# 1.net
KiCad netlist of a schematic drawn in Altium Designer
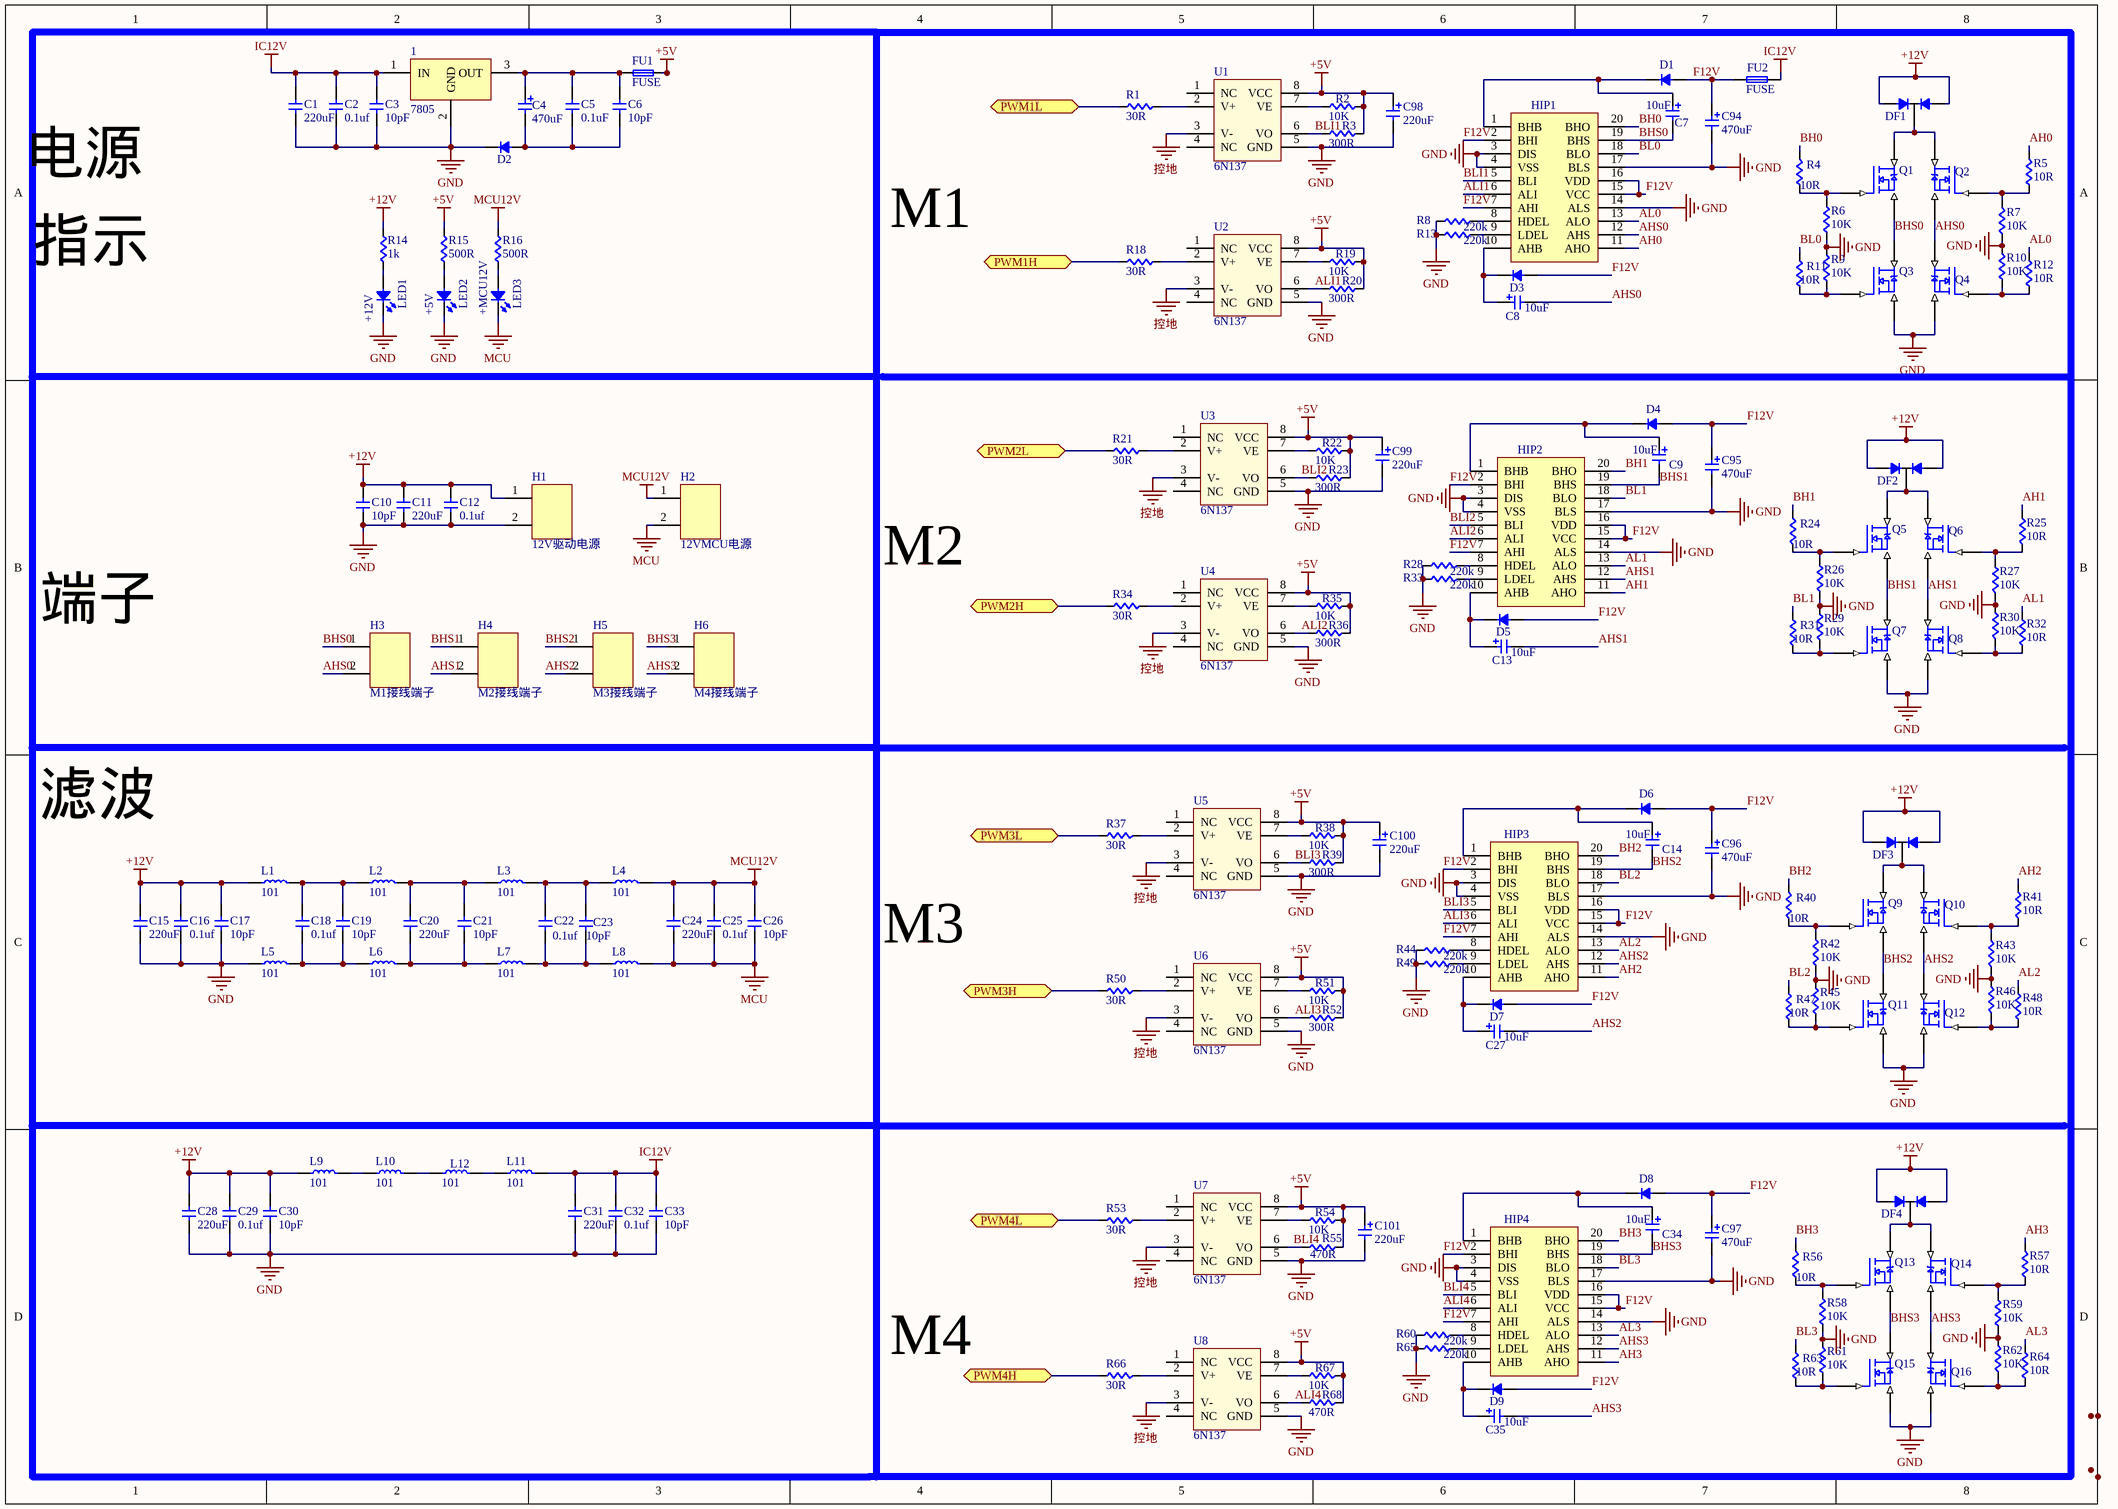
[diagram p0: 小车主板原理图1.SchDoc]

(export (version "E")
  (design (tool "Eeschema 10.0.6"))
  (components
    (comp (ref "1") (value "7805") (footprint "TO-252-2") (libsource (lib "史福祥库") (part "78XX")))
    (comp (ref "C1") (value "220uF") (footprint "CD-8*8-无极性") (libsource (lib "史福祥库") (part "C")))
    (comp (ref "C2") (value "0.1uf") (footprint "0805C") (libsource (lib "史福祥库") (part "C")))
    (comp (ref "C3") (value "10pF") (footprint "0805C") (libsource (lib "史福祥库") (part "C")))
    (comp (ref "C4")
      (value "470uF")
      (footprint "CD-8*8-2")
      (fields (field (name "PUBLISHER") "Altium Limited"))
      (libsource (lib "史福祥库") (part "C+"))
    )
    (comp (ref "C5") (value "0.1uF") (footprint "0805C") (libsource (lib "史福祥库") (part "C")))
    (comp (ref "C6") (value "10pF") (footprint "0805C") (libsource (lib "史福祥库") (part "C")))
    (comp (ref "C7")
      (value "10uF")
      (footprint "CD-8*8-2")
      (fields (field (name "PUBLISHER") "Altium Limited"))
      (libsource (lib "史福祥库") (part "C+"))
    )
    (comp (ref "C8")
      (value "10uF")
      (footprint "CD-8*8-2")
      (fields (field (name "PUBLISHER") "Altium Limited"))
      (libsource (lib "史福祥库") (part "C+"))
    )
    (comp (ref "C9")
      (value "10uF")
      (footprint "CD-8*8-2")
      (fields (field (name "PUBLISHER") "Altium Limited"))
      (libsource (lib "史福祥库") (part "C+"))
    )
    (comp (ref "C10") (value "10pF") (footprint "0805C") (libsource (lib "史福祥库") (part "C")))
    (comp (ref "C11") (value "220uF") (footprint "CD-8*8-无极性") (libsource (lib "史福祥库") (part "C")))
    (comp (ref "C12") (value "0.1uf") (footprint "0805C") (libsource (lib "史福祥库") (part "C")))
    (comp (ref "C13")
      (value "10uF")
      (footprint "CD-8*8-2")
      (fields (field (name "PUBLISHER") "Altium Limited"))
      (libsource (lib "史福祥库") (part "C+"))
    )
    (comp (ref "C14")
      (value "10uF")
      (footprint "CD-8*8-2")
      (fields (field (name "PUBLISHER") "Altium Limited"))
      (libsource (lib "史福祥库") (part "C+"))
    )
    (comp (ref "C15") (value "220uF") (footprint "CD-8*8-无极性") (libsource (lib "史福祥库") (part "C")))
    (comp (ref "C16") (value "0.1uf") (footprint "0805C") (libsource (lib "史福祥库") (part "C")))
    (comp (ref "C17") (value "10pF") (footprint "0805C") (libsource (lib "史福祥库") (part "C")))
    (comp (ref "C18") (value "0.1uf") (footprint "0805C") (libsource (lib "史福祥库") (part "C")))
    (comp (ref "C19") (value "10pF") (footprint "0805C") (libsource (lib "史福祥库") (part "C")))
    (comp (ref "C20") (value "220uF") (footprint "CD-8*8-无极性") (libsource (lib "史福祥库") (part "C")))
    (comp (ref "C21") (value "10pF") (footprint "0805C") (libsource (lib "史福祥库") (part "C")))
    (comp (ref "C22") (value "0.1uf") (footprint "0805C") (libsource (lib "史福祥库") (part "C")))
    (comp (ref "C23") (value "10pF") (footprint "0805C") (libsource (lib "史福祥库") (part "C")))
    (comp (ref "C24") (value "220uF") (footprint "CD-8*8-无极性") (libsource (lib "史福祥库") (part "C")))
    (comp (ref "C25") (value "0.1uf") (footprint "0805C") (libsource (lib "史福祥库") (part "C")))
    (comp (ref "C26") (value "10pF") (footprint "0805C") (libsource (lib "史福祥库") (part "C")))
    (comp (ref "C27")
      (value "10uF")
      (footprint "CD-8*8-2")
      (fields (field (name "PUBLISHER") "Altium Limited"))
      (libsource (lib "史福祥库") (part "C+"))
    )
    (comp (ref "C28") (value "220uF") (footprint "CD-8*8-无极性") (libsource (lib "史福祥库") (part "C")))
    (comp (ref "C29") (value "0.1uf") (footprint "0805C") (libsource (lib "史福祥库") (part "C")))
    (comp (ref "C30") (value "10pF") (footprint "0805C") (libsource (lib "史福祥库") (part "C")))
    (comp (ref "C31") (value "220uF") (footprint "CD-8*8-无极性") (libsource (lib "史福祥库") (part "C")))
    (comp (ref "C32") (value "0.1uf") (footprint "0805C") (libsource (lib "史福祥库") (part "C")))
    (comp (ref "C33") (value "10pF") (footprint "0805C") (libsource (lib "史福祥库") (part "C")))
    (comp (ref "C34")
      (value "10uF")
      (footprint "CD-8*8-2")
      (fields (field (name "PUBLISHER") "Altium Limited"))
      (libsource (lib "史福祥库") (part "C+"))
    )
    (comp (ref "C35")
      (value "10uF")
      (footprint "CD-8*8-2")
      (fields (field (name "PUBLISHER") "Altium Limited"))
      (libsource (lib "史福祥库") (part "C+"))
    )
    (comp (ref "C94")
      (value "470uF")
      (footprint "CD-8*8-2")
      (fields (field (name "PUBLISHER") "Altium Limited"))
      (libsource (lib "史福祥库") (part "C+"))
    )
    (comp (ref "C95")
      (value "470uF")
      (footprint "CD-8*8-2")
      (fields (field (name "PUBLISHER") "Altium Limited"))
      (libsource (lib "史福祥库") (part "C+"))
    )
    (comp (ref "C96")
      (value "470uF")
      (footprint "CD-8*8-2")
      (fields (field (name "PUBLISHER") "Altium Limited"))
      (libsource (lib "史福祥库") (part "C+"))
    )
    (comp (ref "C97")
      (value "470uF")
      (footprint "CD-8*8-2")
      (fields (field (name "PUBLISHER") "Altium Limited"))
      (libsource (lib "史福祥库") (part "C+"))
    )
    (comp (ref "C98")
      (value "220uF")
      (footprint "CD-8*8-2")
      (fields (field (name "PUBLISHER") "Altium Limited"))
      (libsource (lib "史福祥库") (part "C+"))
    )
    (comp (ref "C99")
      (value "220uF")
      (footprint "CD-8*8-2")
      (fields (field (name "PUBLISHER") "Altium Limited"))
      (libsource (lib "史福祥库") (part "C+"))
    )
    (comp (ref "C100")
      (value "220uF")
      (footprint "CD-8*8-2")
      (fields (field (name "PUBLISHER") "Altium Limited"))
      (libsource (lib "史福祥库") (part "C+"))
    )
    (comp (ref "C101")
      (value "220uF")
      (footprint "CD-8*8-2")
      (fields (field (name "PUBLISHER") "Altium Limited"))
      (libsource (lib "史福祥库") (part "C+"))
    )
    (comp (ref "D1")
      (value "D")
      (footprint "DO-214-M7-  4007贴片")
      (fields (field (name "PUBLISHER") "Altium Limited"))
      (libsource (lib "史福祥库") (part "D"))
    )
    (comp (ref "D2")
      (value "D")
      (footprint "DO-214-M7-  4007贴片")
      (fields (field (name "PUBLISHER") "Altium Limited"))
      (libsource (lib "史福祥库") (part "D"))
    )
    (comp (ref "D3")
      (value "D")
      (footprint "DO-214-M7-  4007贴片")
      (fields (field (name "PUBLISHER") "Altium Limited"))
      (libsource (lib "史福祥库") (part "D"))
    )
    (comp (ref "D4")
      (value "D")
      (footprint "DO-214-M7-  4007贴片")
      (fields (field (name "PUBLISHER") "Altium Limited"))
      (libsource (lib "史福祥库") (part "D"))
    )
    (comp (ref "D5")
      (value "D")
      (footprint "DO-214-M7-  4007贴片")
      (fields (field (name "PUBLISHER") "Altium Limited"))
      (libsource (lib "史福祥库") (part "D"))
    )
    (comp (ref "D6")
      (value "D")
      (footprint "DO-214-M7-  4007贴片")
      (fields (field (name "PUBLISHER") "Altium Limited"))
      (libsource (lib "史福祥库") (part "D"))
    )
    (comp (ref "D7")
      (value "D")
      (footprint "DO-214-M7-  4007贴片")
      (fields (field (name "PUBLISHER") "Altium Limited"))
      (libsource (lib "史福祥库") (part "D"))
    )
    (comp (ref "D8")
      (value "D")
      (footprint "DO-214-M7-  4007贴片")
      (fields (field (name "PUBLISHER") "Altium Limited"))
      (libsource (lib "史福祥库") (part "D"))
    )
    (comp (ref "D9")
      (value "D")
      (footprint "DO-214-M7-  4007贴片")
      (fields (field (name "PUBLISHER") "Altium Limited"))
      (libsource (lib "史福祥库") (part "D"))
    )
    (comp (ref "DF1") (value "DF?") (footprint "TO263") (libsource (lib "史福祥库") (part "D复合二极管")))
    (comp (ref "DF2") (value "DF?") (footprint "TO263") (libsource (lib "史福祥库") (part "D复合二极管")))
    (comp (ref "DF3") (value "DF?") (footprint "TO263") (libsource (lib "史福祥库") (part "D复合二极管")))
    (comp (ref "DF4") (value "DF?") (footprint "TO263") (libsource (lib "史福祥库") (part "D复合二极管")))
    (comp (ref "FU1") (value "FUSE") (footprint "1206") (libsource (lib "史福祥库") (part "FUSE")))
    (comp (ref "FU2") (value "FUSE") (footprint "1206") (libsource (lib "史福祥库") (part "FUSE")))
    (comp (ref "H1") (value "12V驱动电源") (footprint "KF301接线端子") (libsource (lib "史福祥库") (part "KF301 接线端子")))
    (comp (ref "H2") (value "12VMCU电源") (footprint "KF301接线端子") (libsource (lib "史福祥库") (part "KF301 接线端子")))
    (comp (ref "H3") (value "M1接线端子") (footprint "KF301接线端子") (libsource (lib "史福祥库") (part "KF301 接线端子")))
    (comp (ref "H4") (value "M2接线端子") (footprint "KF301接线端子") (libsource (lib "史福祥库") (part "KF301 接线端子")))
    (comp (ref "H5") (value "M3接线端子") (footprint "KF301接线端子") (libsource (lib "史福祥库") (part "KF301 接线端子")))
    (comp (ref "H6") (value "M4接线端子") (footprint "KF301接线端子") (libsource (lib "史福祥库") (part "KF301 接线端子")))
    (comp (ref "HIP1") (value "HIP4081") (footprint "SOP-20..") (libsource (lib "史福祥库") (part "HIP4081")))
    (comp (ref "HIP2") (value "HIP4081") (footprint "SOP-20..") (libsource (lib "史福祥库") (part "HIP4081")))
    (comp (ref "HIP3") (value "HIP4081") (footprint "SOP-20..") (libsource (lib "史福祥库") (part "HIP4081")))
    (comp (ref "HIP4") (value "HIP4081") (footprint "SOP-20..") (libsource (lib "史福祥库") (part "HIP4081")))
    (comp (ref "L1")
      (value "101")
      (footprint "12*12电感")
      (fields (field (name "Comment") "L") (field (name "PUBLISHER") "Altium Limited"))
      (libsource (lib "史福祥库") (part "L"))
    )
    (comp (ref "L2")
      (value "101")
      (footprint "12*12电感")
      (fields (field (name "Comment") "L") (field (name "PUBLISHER") "Altium Limited"))
      (libsource (lib "史福祥库") (part "L"))
    )
    (comp (ref "L3")
      (value "101")
      (footprint "12*12电感")
      (fields (field (name "Comment") "L") (field (name "PUBLISHER") "Altium Limited"))
      (libsource (lib "史福祥库") (part "L"))
    )
    (comp (ref "L4")
      (value "101")
      (footprint "12*12电感")
      (fields (field (name "Comment") "L") (field (name "PUBLISHER") "Altium Limited"))
      (libsource (lib "史福祥库") (part "L"))
    )
    (comp (ref "L5")
      (value "101")
      (footprint "12*12电感")
      (fields (field (name "Comment") "L") (field (name "PUBLISHER") "Altium Limited"))
      (libsource (lib "史福祥库") (part "L"))
    )
    (comp (ref "L6")
      (value "101")
      (footprint "12*12电感")
      (fields (field (name "Comment") "L") (field (name "PUBLISHER") "Altium Limited"))
      (libsource (lib "史福祥库") (part "L"))
    )
    (comp (ref "L7")
      (value "101")
      (footprint "12*12电感")
      (fields (field (name "Comment") "L") (field (name "PUBLISHER") "Altium Limited"))
      (libsource (lib "史福祥库") (part "L"))
    )
    (comp (ref "L8")
      (value "101")
      (footprint "12*12电感")
      (fields (field (name "Comment") "L") (field (name "PUBLISHER") "Altium Limited"))
      (libsource (lib "史福祥库") (part "L"))
    )
    (comp (ref "L9")
      (value "101")
      (footprint "12*12电感")
      (fields (field (name "Comment") "L") (field (name "PUBLISHER") "Altium Limited"))
      (libsource (lib "史福祥库") (part "L"))
    )
    (comp (ref "L10")
      (value "101")
      (footprint "12*12电感")
      (fields (field (name "Comment") "L") (field (name "PUBLISHER") "Altium Limited"))
      (libsource (lib "史福祥库") (part "L"))
    )
    (comp (ref "L11")
      (value "101")
      (footprint "12*12电感")
      (fields (field (name "Comment") "L") (field (name "PUBLISHER") "Altium Limited"))
      (libsource (lib "史福祥库") (part "L"))
    )
    (comp (ref "L12")
      (value "101")
      (footprint "12*12电感")
      (fields (field (name "Comment") "L") (field (name "PUBLISHER") "Altium Limited"))
      (libsource (lib "史福祥库") (part "L"))
    )
    (comp (ref "LED1")
      (value "+12V")
      (footprint "0805D")
      (fields (field (name "PUBLISHER") "Altium Limited"))
      (libsource (lib "史福祥库") (part "LED"))
    )
    (comp (ref "LED2")
      (value "+5V")
      (footprint "0805D")
      (fields (field (name "PUBLISHER") "Altium Limited"))
      (libsource (lib "史福祥库") (part "LED"))
    )
    (comp (ref "LED3")
      (value "+MCU12V")
      (footprint "0805D")
      (fields (field (name "PUBLISHER") "Altium Limited"))
      (libsource (lib "史福祥库") (part "LED"))
    )
    (comp (ref "Q1") (value "IRFP260N") (footprint "TO-247 - 贴") (libsource (lib "史福祥库") (part "IRFP260N")))
    (comp (ref "Q2") (value "IRFP260N") (footprint "TO-247 - 贴") (libsource (lib "史福祥库") (part "IRFP260N")))
    (comp (ref "Q3") (value "IRFP260N") (footprint "TO-247 - 贴") (libsource (lib "史福祥库") (part "IRFP260N")))
    (comp (ref "Q4") (value "IRFP260N") (footprint "TO-247 - 贴") (libsource (lib "史福祥库") (part "IRFP260N")))
    (comp (ref "Q5") (value "IRFP260N") (footprint "TO-247 - 贴") (libsource (lib "史福祥库") (part "IRFP260N")))
    (comp (ref "Q6") (value "IRFP260N") (footprint "TO-247 - 贴") (libsource (lib "史福祥库") (part "IRFP260N")))
    (comp (ref "Q7") (value "IRFP260N") (footprint "TO-247 - 贴") (libsource (lib "史福祥库") (part "IRFP260N")))
    (comp (ref "Q8") (value "IRFP260N") (footprint "TO-247 - 贴") (libsource (lib "史福祥库") (part "IRFP260N")))
    (comp (ref "Q9") (value "IRFP260N") (footprint "TO-247 - 贴") (libsource (lib "史福祥库") (part "IRFP260N")))
    (comp (ref "Q10") (value "IRFP260N") (footprint "TO-247 - 贴") (libsource (lib "史福祥库") (part "IRFP260N")))
    (comp (ref "Q11") (value "IRFP260N") (footprint "TO-247 - 贴") (libsource (lib "史福祥库") (part "IRFP260N")))
    (comp (ref "Q12") (value "IRFP260N") (footprint "TO-247 - 贴") (libsource (lib "史福祥库") (part "IRFP260N")))
    (comp (ref "Q13") (value "IRFP260N") (footprint "TO-247 - 贴") (libsource (lib "史福祥库") (part "IRFP260N")))
    (comp (ref "Q14") (value "IRFP260N") (footprint "TO-247 - 贴") (libsource (lib "史福祥库") (part "IRFP260N")))
    (comp (ref "Q15") (value "IRFP260N") (footprint "TO-247 - 贴") (libsource (lib "史福祥库") (part "IRFP260N")))
    (comp (ref "Q16") (value "IRFP260N") (footprint "TO-247 - 贴") (libsource (lib "史福祥库") (part "IRFP260N")))
    (comp (ref "R1") (value "30R") (footprint "0805") (libsource (lib "史福祥库") (part "Res")))
    (comp (ref "R2") (value "10K") (footprint "0805") (libsource (lib "史福祥库") (part "Res")))
    (comp (ref "R3") (value "300R") (footprint "0805") (libsource (lib "史福祥库") (part "Res")))
    (comp (ref "R4") (value "10R") (footprint "0805") (libsource (lib "史福祥库") (part "Res")))
    (comp (ref "R5") (value "10R") (footprint "0805") (libsource (lib "史福祥库") (part "Res")))
    (comp (ref "R6") (value "10K") (footprint "0805") (libsource (lib "史福祥库") (part "Res")))
    (comp (ref "R7") (value "10K") (footprint "0805") (libsource (lib "史福祥库") (part "Res")))
    (comp (ref "R8") (value "220k") (footprint "0805") (libsource (lib "史福祥库") (part "Res")))
    (comp (ref "R9") (value "10K") (footprint "0805") (libsource (lib "史福祥库") (part "Res")))
    (comp (ref "R10") (value "10K") (footprint "0805") (libsource (lib "史福祥库") (part "Res")))
    (comp (ref "R11") (value "10R") (footprint "0805") (libsource (lib "史福祥库") (part "Res")))
    (comp (ref "R12") (value "10R") (footprint "0805") (libsource (lib "史福祥库") (part "Res")))
    (comp (ref "R13") (value "220k") (footprint "0805") (libsource (lib "史福祥库") (part "Res")))
    (comp (ref "R14") (value "1k") (footprint "0805") (libsource (lib "史福祥库") (part "Res")))
    (comp (ref "R15") (value "500R") (footprint "0805") (libsource (lib "史福祥库") (part "Res")))
    (comp (ref "R16") (value "500R") (footprint "0805") (libsource (lib "史福祥库") (part "Res")))
    (comp (ref "R18") (value "30R") (footprint "0805") (libsource (lib "史福祥库") (part "Res")))
    (comp (ref "R19") (value "10K") (footprint "0805") (libsource (lib "史福祥库") (part "Res")))
    (comp (ref "R20") (value "300R") (footprint "0805") (libsource (lib "史福祥库") (part "Res")))
    (comp (ref "R21") (value "30R") (footprint "0805") (libsource (lib "史福祥库") (part "Res")))
    (comp (ref "R22") (value "10K") (footprint "0805") (libsource (lib "史福祥库") (part "Res")))
    (comp (ref "R23") (value "300R") (footprint "0805") (libsource (lib "史福祥库") (part "Res")))
    (comp (ref "R24") (value "10R") (footprint "0805") (libsource (lib "史福祥库") (part "Res")))
    (comp (ref "R25") (value "10R") (footprint "0805") (libsource (lib "史福祥库") (part "Res")))
    (comp (ref "R26") (value "10K") (footprint "0805") (libsource (lib "史福祥库") (part "Res")))
    (comp (ref "R27") (value "10K") (footprint "0805") (libsource (lib "史福祥库") (part "Res")))
    (comp (ref "R28") (value "220k") (footprint "0805") (libsource (lib "史福祥库") (part "Res")))
    (comp (ref "R29") (value "10K") (footprint "0805") (libsource (lib "史福祥库") (part "Res")))
    (comp (ref "R30") (value "10K") (footprint "0805") (libsource (lib "史福祥库") (part "Res")))
    (comp (ref "R31") (value "10R") (footprint "0805") (libsource (lib "史福祥库") (part "Res")))
    (comp (ref "R32") (value "10R") (footprint "0805") (libsource (lib "史福祥库") (part "Res")))
    (comp (ref "R33") (value "220k") (footprint "0805") (libsource (lib "史福祥库") (part "Res")))
    (comp (ref "R34") (value "30R") (footprint "0805") (libsource (lib "史福祥库") (part "Res")))
    (comp (ref "R35") (value "10K") (footprint "0805") (libsource (lib "史福祥库") (part "Res")))
    (comp (ref "R36") (value "300R") (footprint "0805") (libsource (lib "史福祥库") (part "Res")))
    (comp (ref "R37") (value "30R") (footprint "0805") (libsource (lib "史福祥库") (part "Res")))
    (comp (ref "R38") (value "10K") (footprint "0805") (libsource (lib "史福祥库") (part "Res")))
    (comp (ref "R39") (value "300R") (footprint "0805") (libsource (lib "史福祥库") (part "Res")))
    (comp (ref "R40") (value "10R") (footprint "0805") (libsource (lib "史福祥库") (part "Res")))
    (comp (ref "R41") (value "10R") (footprint "0805") (libsource (lib "史福祥库") (part "Res")))
    (comp (ref "R42") (value "10K") (footprint "0805") (libsource (lib "史福祥库") (part "Res")))
    (comp (ref "R43") (value "10K") (footprint "0805") (libsource (lib "史福祥库") (part "Res")))
    (comp (ref "R44") (value "220k") (footprint "0805") (libsource (lib "史福祥库") (part "Res")))
    (comp (ref "R45") (value "10K") (footprint "0805") (libsource (lib "史福祥库") (part "Res")))
    (comp (ref "R46") (value "10K") (footprint "0805") (libsource (lib "史福祥库") (part "Res")))
    (comp (ref "R47") (value "10R") (footprint "0805") (libsource (lib "史福祥库") (part "Res")))
    (comp (ref "R48") (value "10R") (footprint "0805") (libsource (lib "史福祥库") (part "Res")))
    (comp (ref "R49") (value "220k") (footprint "0805") (libsource (lib "史福祥库") (part "Res")))
    (comp (ref "R50") (value "30R") (footprint "0805") (libsource (lib "史福祥库") (part "Res")))
    (comp (ref "R51") (value "10K") (footprint "0805") (libsource (lib "史福祥库") (part "Res")))
    (comp (ref "R52") (value "300R") (footprint "0805") (libsource (lib "史福祥库") (part "Res")))
    (comp (ref "R53") (value "30R") (footprint "0805") (libsource (lib "史福祥库") (part "Res")))
    (comp (ref "R54") (value "10K") (footprint "0805") (libsource (lib "史福祥库") (part "Res")))
    (comp (ref "R55") (value "470R") (footprint "0805") (libsource (lib "史福祥库") (part "Res")))
    (comp (ref "R56") (value "10R") (footprint "0805") (libsource (lib "史福祥库") (part "Res")))
    (comp (ref "R57") (value "10R") (footprint "0805") (libsource (lib "史福祥库") (part "Res")))
    (comp (ref "R58") (value "10K") (footprint "0805") (libsource (lib "史福祥库") (part "Res")))
    (comp (ref "R59") (value "10K") (footprint "0805") (libsource (lib "史福祥库") (part "Res")))
    (comp (ref "R60") (value "220k") (footprint "0805") (libsource (lib "史福祥库") (part "Res")))
    (comp (ref "R61") (value "10K") (footprint "0805") (libsource (lib "史福祥库") (part "Res")))
    (comp (ref "R62") (value "10K") (footprint "0805") (libsource (lib "史福祥库") (part "Res")))
    (comp (ref "R63") (value "10R") (footprint "0805") (libsource (lib "史福祥库") (part "Res")))
    (comp (ref "R64") (value "10R") (footprint "0805") (libsource (lib "史福祥库") (part "Res")))
    (comp (ref "R65") (value "220k") (footprint "0805") (libsource (lib "史福祥库") (part "Res")))
    (comp (ref "R66") (value "30R") (footprint "0805") (libsource (lib "史福祥库") (part "Res")))
    (comp (ref "R67") (value "10K") (footprint "0805") (libsource (lib "史福祥库") (part "Res")))
    (comp (ref "R68") (value "470R") (footprint "0805") (libsource (lib "史福祥库") (part "Res")))
    (comp (ref "U1") (value "6N137") (footprint "SOP-8") (libsource (lib "史福祥库") (part "6N137")))
    (comp (ref "U2") (value "6N137") (footprint "SOP-8") (libsource (lib "史福祥库") (part "6N137")))
    (comp (ref "U3") (value "6N137") (footprint "SOP-8") (libsource (lib "史福祥库") (part "6N137")))
    (comp (ref "U4") (value "6N137") (footprint "SOP-8") (libsource (lib "史福祥库") (part "6N137")))
    (comp (ref "U5") (value "6N137") (footprint "SOP-8") (libsource (lib "史福祥库") (part "6N137")))
    (comp (ref "U6") (value "6N137") (footprint "SOP-8") (libsource (lib "史福祥库") (part "6N137")))
    (comp (ref "U7") (value "6N137") (footprint "SOP-8") (libsource (lib "史福祥库") (part "6N137")))
    (comp (ref "U8") (value "6N137") (footprint "SOP-8") (libsource (lib "史福祥库") (part "6N137")))
  )
  (nets
    (net (code "1") (name "+5V") (class "Default")
      (node (ref "C100") (pin "1") (pinfunction "1_1") (pintype "passive"))
      (node (ref "C101") (pin "1") (pinfunction "1_1") (pintype "passive"))
      (node (ref "C98") (pin "1") (pinfunction "1_1") (pintype "passive"))
      (node (ref "C99") (pin "1") (pinfunction "1_1") (pintype "passive"))
      (node (ref "FU1") (pin "2") (pinfunction "2_2") (pintype "passive"))
      (node (ref "R15") (pin "2") (pinfunction "2_2") (pintype "passive"))
      (node (ref "R19") (pin "1") (pinfunction "1_1") (pintype "passive"))
      (node (ref "R2") (pin "1") (pinfunction "1_1") (pintype "passive"))
      (node (ref "R20") (pin "1") (pinfunction "1_1") (pintype "passive"))
      (node (ref "R22") (pin "1") (pinfunction "1_1") (pintype "passive"))
      (node (ref "R23") (pin "1") (pinfunction "1_1") (pintype "passive"))
      (node (ref "R3") (pin "1") (pinfunction "1_1") (pintype "passive"))
      (node (ref "R35") (pin "1") (pinfunction "1_1") (pintype "passive"))
      (node (ref "R36") (pin "1") (pinfunction "1_1") (pintype "passive"))
      (node (ref "R38") (pin "1") (pinfunction "1_1") (pintype "passive"))
      (node (ref "R39") (pin "1") (pinfunction "1_1") (pintype "passive"))
      (node (ref "R51") (pin "1") (pinfunction "1_1") (pintype "passive"))
      (node (ref "R52") (pin "1") (pinfunction "1_1") (pintype "passive"))
      (node (ref "R54") (pin "1") (pinfunction "1_1") (pintype "passive"))
      (node (ref "R55") (pin "1") (pinfunction "1_1") (pintype "passive"))
      (node (ref "R67") (pin "1") (pinfunction "1_1") (pintype "passive"))
      (node (ref "R68") (pin "1") (pinfunction "1_1") (pintype "passive"))
      (node (ref "U1") (pin "8") (pinfunction "VCC_8") (pintype "passive"))
      (node (ref "U2") (pin "8") (pinfunction "VCC_8") (pintype "passive"))
      (node (ref "U3") (pin "8") (pinfunction "VCC_8") (pintype "passive"))
      (node (ref "U4") (pin "8") (pinfunction "VCC_8") (pintype "passive"))
      (node (ref "U5") (pin "8") (pinfunction "VCC_8") (pintype "passive"))
      (node (ref "U6") (pin "8") (pinfunction "VCC_8") (pintype "passive"))
      (node (ref "U7") (pin "8") (pinfunction "VCC_8") (pintype "passive"))
      (node (ref "U8") (pin "8") (pinfunction "VCC_8") (pintype "passive"))
    )
    (net (code "2") (name "+12V") (class "Default")
      (node (ref "C10") (pin "2") (pinfunction "2_2") (pintype "passive"))
      (node (ref "C11") (pin "2") (pinfunction "2_2") (pintype "passive"))
      (node (ref "C12") (pin "2") (pinfunction "2_2") (pintype "passive"))
      (node (ref "C15") (pin "2") (pinfunction "2_2") (pintype "passive"))
      (node (ref "C16") (pin "2") (pinfunction "2_2") (pintype "passive"))
      (node (ref "C17") (pin "2") (pinfunction "2_2") (pintype "passive"))
      (node (ref "C28") (pin "2") (pinfunction "2_2") (pintype "passive"))
      (node (ref "C29") (pin "2") (pinfunction "2_2") (pintype "passive"))
      (node (ref "C30") (pin "2") (pinfunction "2_2") (pintype "passive"))
      (node (ref "DF1") (pin "1") (pinfunction "A_1") (pintype "passive"))
      (node (ref "DF1") (pin "3") (pinfunction "C_3") (pintype "passive"))
      (node (ref "DF2") (pin "1") (pinfunction "A_1") (pintype "passive"))
      (node (ref "DF2") (pin "3") (pinfunction "C_3") (pintype "passive"))
      (node (ref "DF3") (pin "1") (pinfunction "A_1") (pintype "passive"))
      (node (ref "DF3") (pin "3") (pinfunction "C_3") (pintype "passive"))
      (node (ref "DF4") (pin "1") (pinfunction "A_1") (pintype "passive"))
      (node (ref "DF4") (pin "3") (pinfunction "C_3") (pintype "passive"))
      (node (ref "H1") (pin "1") (pintype "passive"))
      (node (ref "L1") (pin "1") (pinfunction "1_1") (pintype "passive"))
      (node (ref "L9") (pin "1") (pinfunction "1_1") (pintype "passive"))
      (node (ref "R14") (pin "2") (pinfunction "2_2") (pintype "passive"))
    )
    (net (code "3") (name "/AH0") (class "Default")
      (node (ref "HIP1") (pin "11") (pinfunction "AHO_11") (pintype "tri_state"))
      (node (ref "R5") (pin "2") (pinfunction "2_2") (pintype "passive"))
    )
    (net (code "4") (name "/AH1") (class "Default")
      (node (ref "HIP2") (pin "11") (pinfunction "AHO_11") (pintype "tri_state"))
      (node (ref "R25") (pin "2") (pinfunction "2_2") (pintype "passive"))
    )
    (net (code "5") (name "/AH2") (class "Default")
      (node (ref "HIP3") (pin "11") (pinfunction "AHO_11") (pintype "tri_state"))
      (node (ref "R41") (pin "2") (pinfunction "2_2") (pintype "passive"))
    )
    (net (code "6") (name "/AH3") (class "Default")
      (node (ref "HIP4") (pin "11") (pinfunction "AHO_11") (pintype "tri_state"))
      (node (ref "R57") (pin "2") (pinfunction "2_2") (pintype "passive"))
    )
    (net (code "7") (name "/AHS0") (class "Default")
      (node (ref "C8") (pin "2") (pinfunction "2_2") (pintype "passive"))
      (node (ref "H3") (pin "2") (pintype "passive"))
      (node (ref "HIP1") (pin "12") (pinfunction "AHS_12") (pintype "tri_state"))
      (node (ref "Q2") (pin "3") (pinfunction "S_3") (pintype "input"))
      (node (ref "Q4") (pin "2") (pinfunction "D_2") (pintype "input"))
    )
    (net (code "8") (name "/AHS1") (class "Default")
      (node (ref "C13") (pin "2") (pinfunction "2_2") (pintype "passive"))
      (node (ref "H4") (pin "2") (pintype "passive"))
      (node (ref "HIP2") (pin "12") (pinfunction "AHS_12") (pintype "tri_state"))
      (node (ref "Q6") (pin "3") (pinfunction "S_3") (pintype "input"))
      (node (ref "Q8") (pin "2") (pinfunction "D_2") (pintype "input"))
    )
    (net (code "9") (name "/AHS2") (class "Default")
      (node (ref "C27") (pin "2") (pinfunction "2_2") (pintype "passive"))
      (node (ref "H5") (pin "2") (pintype "passive"))
      (node (ref "HIP3") (pin "12") (pinfunction "AHS_12") (pintype "tri_state"))
      (node (ref "Q10") (pin "3") (pinfunction "S_3") (pintype "input"))
      (node (ref "Q12") (pin "2") (pinfunction "D_2") (pintype "input"))
    )
    (net (code "10") (name "/AHS3") (class "Default")
      (node (ref "C35") (pin "2") (pinfunction "2_2") (pintype "passive"))
      (node (ref "H6") (pin "2") (pintype "passive"))
      (node (ref "HIP4") (pin "12") (pinfunction "AHS_12") (pintype "tri_state"))
      (node (ref "Q14") (pin "3") (pinfunction "S_3") (pintype "input"))
      (node (ref "Q16") (pin "2") (pinfunction "D_2") (pintype "input"))
    )
    (net (code "11") (name "/AL0") (class "Default")
      (node (ref "HIP1") (pin "13") (pinfunction "ALO_13") (pintype "tri_state"))
      (node (ref "R12") (pin "2") (pinfunction "2_2") (pintype "passive"))
    )
    (net (code "12") (name "/AL1") (class "Default")
      (node (ref "HIP2") (pin "13") (pinfunction "ALO_13") (pintype "tri_state"))
      (node (ref "R32") (pin "2") (pinfunction "2_2") (pintype "passive"))
    )
    (net (code "13") (name "/AL2") (class "Default")
      (node (ref "HIP3") (pin "13") (pinfunction "ALO_13") (pintype "tri_state"))
      (node (ref "R48") (pin "2") (pinfunction "2_2") (pintype "passive"))
    )
    (net (code "14") (name "/AL3") (class "Default")
      (node (ref "HIP4") (pin "13") (pinfunction "ALO_13") (pintype "tri_state"))
      (node (ref "R64") (pin "2") (pinfunction "2_2") (pintype "passive"))
    )
    (net (code "15") (name "/ALI1") (class "Default")
      (node (ref "HIP1") (pin "6") (pinfunction "ALI_6") (pintype "tri_state"))
      (node (ref "R20") (pin "2") (pinfunction "2_2") (pintype "passive"))
      (node (ref "U2") (pin "6") (pinfunction "VO_6") (pintype "passive"))
    )
    (net (code "16") (name "/ALI2") (class "Default")
      (node (ref "HIP2") (pin "6") (pinfunction "ALI_6") (pintype "tri_state"))
      (node (ref "R36") (pin "2") (pinfunction "2_2") (pintype "passive"))
      (node (ref "U4") (pin "6") (pinfunction "VO_6") (pintype "passive"))
    )
    (net (code "17") (name "/ALI3") (class "Default")
      (node (ref "HIP3") (pin "6") (pinfunction "ALI_6") (pintype "tri_state"))
      (node (ref "R52") (pin "2") (pinfunction "2_2") (pintype "passive"))
      (node (ref "U6") (pin "6") (pinfunction "VO_6") (pintype "passive"))
    )
    (net (code "18") (name "/ALI4") (class "Default")
      (node (ref "HIP4") (pin "6") (pinfunction "ALI_6") (pintype "tri_state"))
      (node (ref "R68") (pin "2") (pinfunction "2_2") (pintype "passive"))
      (node (ref "U8") (pin "6") (pinfunction "VO_6") (pintype "passive"))
    )
    (net (code "19") (name "/BH0") (class "Default")
      (node (ref "HIP1") (pin "20") (pinfunction "BHO_20") (pintype "tri_state"))
      (node (ref "R4") (pin "1") (pinfunction "1_1") (pintype "passive"))
    )
    (net (code "20") (name "/BH1") (class "Default")
      (node (ref "HIP2") (pin "20") (pinfunction "BHO_20") (pintype "tri_state"))
      (node (ref "R24") (pin "1") (pinfunction "1_1") (pintype "passive"))
    )
    (net (code "21") (name "/BH2") (class "Default")
      (node (ref "HIP3") (pin "20") (pinfunction "BHO_20") (pintype "tri_state"))
      (node (ref "R40") (pin "1") (pinfunction "1_1") (pintype "passive"))
    )
    (net (code "22") (name "/BH3") (class "Default")
      (node (ref "HIP4") (pin "20") (pinfunction "BHO_20") (pintype "tri_state"))
      (node (ref "R56") (pin "1") (pinfunction "1_1") (pintype "passive"))
    )
    (net (code "23") (name "/BHS0") (class "Default")
      (node (ref "C7") (pin "2") (pinfunction "2_2") (pintype "passive"))
      (node (ref "H3") (pin "1") (pintype "passive"))
      (node (ref "HIP1") (pin "19") (pinfunction "BHS_19") (pintype "tri_state"))
      (node (ref "Q1") (pin "3") (pinfunction "S_3") (pintype "input"))
      (node (ref "Q3") (pin "2") (pinfunction "D_2") (pintype "input"))
    )
    (net (code "24") (name "/BHS1") (class "Default")
      (node (ref "C9") (pin "2") (pinfunction "2_2") (pintype "passive"))
      (node (ref "H4") (pin "1") (pintype "passive"))
      (node (ref "HIP2") (pin "19") (pinfunction "BHS_19") (pintype "tri_state"))
      (node (ref "Q5") (pin "3") (pinfunction "S_3") (pintype "input"))
      (node (ref "Q7") (pin "2") (pinfunction "D_2") (pintype "input"))
    )
    (net (code "25") (name "/BHS2") (class "Default")
      (node (ref "C14") (pin "2") (pinfunction "2_2") (pintype "passive"))
      (node (ref "H5") (pin "1") (pintype "passive"))
      (node (ref "HIP3") (pin "19") (pinfunction "BHS_19") (pintype "tri_state"))
      (node (ref "Q11") (pin "2") (pinfunction "D_2") (pintype "input"))
      (node (ref "Q9") (pin "3") (pinfunction "S_3") (pintype "input"))
    )
    (net (code "26") (name "/BHS3") (class "Default")
      (node (ref "C34") (pin "2") (pinfunction "2_2") (pintype "passive"))
      (node (ref "H6") (pin "1") (pintype "passive"))
      (node (ref "HIP4") (pin "19") (pinfunction "BHS_19") (pintype "tri_state"))
      (node (ref "Q13") (pin "3") (pinfunction "S_3") (pintype "input"))
      (node (ref "Q15") (pin "2") (pinfunction "D_2") (pintype "input"))
    )
    (net (code "27") (name "/BL0") (class "Default")
      (node (ref "HIP1") (pin "18") (pinfunction "BLO_18") (pintype "tri_state"))
      (node (ref "R11") (pin "2") (pinfunction "2_2") (pintype "passive"))
    )
    (net (code "28") (name "/BL1") (class "Default")
      (node (ref "HIP2") (pin "18") (pinfunction "BLO_18") (pintype "tri_state"))
      (node (ref "R31") (pin "2") (pinfunction "2_2") (pintype "passive"))
    )
    (net (code "29") (name "/BL2") (class "Default")
      (node (ref "HIP3") (pin "18") (pinfunction "BLO_18") (pintype "tri_state"))
      (node (ref "R47") (pin "2") (pinfunction "2_2") (pintype "passive"))
    )
    (net (code "30") (name "/BL3") (class "Default")
      (node (ref "HIP4") (pin "18") (pinfunction "BLO_18") (pintype "tri_state"))
      (node (ref "R63") (pin "2") (pinfunction "2_2") (pintype "passive"))
    )
    (net (code "31") (name "/BLI1") (class "Default")
      (node (ref "HIP1") (pin "5") (pinfunction "BLI_5") (pintype "tri_state"))
      (node (ref "R3") (pin "2") (pinfunction "2_2") (pintype "passive"))
      (node (ref "U1") (pin "6") (pinfunction "VO_6") (pintype "passive"))
    )
    (net (code "32") (name "/BLI2") (class "Default")
      (node (ref "HIP2") (pin "5") (pinfunction "BLI_5") (pintype "tri_state"))
      (node (ref "R23") (pin "2") (pinfunction "2_2") (pintype "passive"))
      (node (ref "U3") (pin "6") (pinfunction "VO_6") (pintype "passive"))
    )
    (net (code "33") (name "/BLI3") (class "Default")
      (node (ref "HIP3") (pin "5") (pinfunction "BLI_5") (pintype "tri_state"))
      (node (ref "R39") (pin "2") (pinfunction "2_2") (pintype "passive"))
      (node (ref "U5") (pin "6") (pinfunction "VO_6") (pintype "passive"))
    )
    (net (code "34") (name "/BLI4") (class "Default")
      (node (ref "HIP4") (pin "5") (pinfunction "BLI_5") (pintype "tri_state"))
      (node (ref "R55") (pin "2") (pinfunction "2_2") (pintype "passive"))
      (node (ref "U7") (pin "6") (pinfunction "VO_6") (pintype "passive"))
    )
    (net (code "35") (name "/F12V") (class "Default")
      (node (ref "C94") (pin "1") (pinfunction "1_1") (pintype "passive"))
      (node (ref "C95") (pin "1") (pinfunction "1_1") (pintype "passive"))
      (node (ref "C96") (pin "1") (pinfunction "1_1") (pintype "passive"))
      (node (ref "C97") (pin "1") (pinfunction "1_1") (pintype "passive"))
      (node (ref "D1") (pin "1") (pinfunction "A_1") (pintype "passive"))
      (node (ref "D3") (pin "1") (pinfunction "A_1") (pintype "passive"))
      (node (ref "D4") (pin "1") (pinfunction "A_1") (pintype "passive"))
      (node (ref "D5") (pin "1") (pinfunction "A_1") (pintype "passive"))
      (node (ref "D6") (pin "1") (pinfunction "A_1") (pintype "passive"))
      (node (ref "D7") (pin "1") (pinfunction "A_1") (pintype "passive"))
      (node (ref "D8") (pin "1") (pinfunction "A_1") (pintype "passive"))
      (node (ref "D9") (pin "1") (pinfunction "A_1") (pintype "passive"))
      (node (ref "FU2") (pin "1") (pinfunction "1_1") (pintype "passive"))
      (node (ref "HIP1") (pin "15") (pinfunction "VCC_15") (pintype "tri_state"))
      (node (ref "HIP1") (pin "16") (pinfunction "VDD_16") (pintype "tri_state"))
      (node (ref "HIP1") (pin "2") (pinfunction "BHI_2") (pintype "tri_state"))
      (node (ref "HIP1") (pin "7") (pinfunction "AHI_7") (pintype "tri_state"))
      (node (ref "HIP2") (pin "15") (pinfunction "VCC_15") (pintype "tri_state"))
      (node (ref "HIP2") (pin "16") (pinfunction "VDD_16") (pintype "tri_state"))
      (node (ref "HIP2") (pin "2") (pinfunction "BHI_2") (pintype "tri_state"))
      (node (ref "HIP2") (pin "7") (pinfunction "AHI_7") (pintype "tri_state"))
      (node (ref "HIP3") (pin "15") (pinfunction "VCC_15") (pintype "tri_state"))
      (node (ref "HIP3") (pin "16") (pinfunction "VDD_16") (pintype "tri_state"))
      (node (ref "HIP3") (pin "2") (pinfunction "BHI_2") (pintype "tri_state"))
      (node (ref "HIP3") (pin "7") (pinfunction "AHI_7") (pintype "tri_state"))
      (node (ref "HIP4") (pin "15") (pinfunction "VCC_15") (pintype "tri_state"))
      (node (ref "HIP4") (pin "16") (pinfunction "VDD_16") (pintype "tri_state"))
      (node (ref "HIP4") (pin "2") (pinfunction "BHI_2") (pintype "tri_state"))
      (node (ref "HIP4") (pin "7") (pinfunction "AHI_7") (pintype "tri_state"))
    )
    (net (code "36") (name "/PWM1H") (class "Default")
      (node (ref "R18") (pin "1") (pinfunction "1_1") (pintype "passive"))
    )
    (net (code "37") (name "/PWM1L") (class "Default")
      (node (ref "R1") (pin "1") (pinfunction "1_1") (pintype "passive"))
    )
    (net (code "38") (name "/PWM2H") (class "Default")
      (node (ref "R34") (pin "1") (pinfunction "1_1") (pintype "passive"))
    )
    (net (code "39") (name "/PWM2L") (class "Default")
      (node (ref "R21") (pin "1") (pinfunction "1_1") (pintype "passive"))
    )
    (net (code "40") (name "/PWM3H") (class "Default")
      (node (ref "R50") (pin "1") (pinfunction "1_1") (pintype "passive"))
    )
    (net (code "41") (name "/PWM3L") (class "Default")
      (node (ref "R37") (pin "1") (pinfunction "1_1") (pintype "passive"))
    )
    (net (code "42") (name "/PWM4H") (class "Default")
      (node (ref "R66") (pin "1") (pinfunction "1_1") (pintype "passive"))
    )
    (net (code "43") (name "/PWM4L") (class "Default")
      (node (ref "R53") (pin "1") (pinfunction "1_1") (pintype "passive"))
    )
    (net (code "44") (name "GND") (class "Default")
      (node (ref "1") (pin "2") (pinfunction "GND_2") (pintype "passive"))
      (node (ref "C1") (pin "1") (pinfunction "1_1") (pintype "passive"))
      (node (ref "C10") (pin "1") (pinfunction "1_1") (pintype "passive"))
      (node (ref "C100") (pin "2") (pinfunction "2_2") (pintype "passive"))
      (node (ref "C101") (pin "2") (pinfunction "2_2") (pintype "passive"))
      (node (ref "C11") (pin "1") (pinfunction "1_1") (pintype "passive"))
      (node (ref "C12") (pin "1") (pinfunction "1_1") (pintype "passive"))
      (node (ref "C15") (pin "1") (pinfunction "1_1") (pintype "passive"))
      (node (ref "C16") (pin "1") (pinfunction "1_1") (pintype "passive"))
      (node (ref "C17") (pin "1") (pinfunction "1_1") (pintype "passive"))
      (node (ref "C2") (pin "1") (pinfunction "1_1") (pintype "passive"))
      (node (ref "C28") (pin "1") (pinfunction "1_1") (pintype "passive"))
      (node (ref "C29") (pin "1") (pinfunction "1_1") (pintype "passive"))
      (node (ref "C3") (pin "1") (pinfunction "1_1") (pintype "passive"))
      (node (ref "C30") (pin "1") (pinfunction "1_1") (pintype "passive"))
      (node (ref "C31") (pin "1") (pinfunction "1_1") (pintype "passive"))
      (node (ref "C32") (pin "1") (pinfunction "1_1") (pintype "passive"))
      (node (ref "C33") (pin "1") (pinfunction "1_1") (pintype "passive"))
      (node (ref "C94") (pin "2") (pinfunction "2_2") (pintype "passive"))
      (node (ref "C95") (pin "2") (pinfunction "2_2") (pintype "passive"))
      (node (ref "C96") (pin "2") (pinfunction "2_2") (pintype "passive"))
      (node (ref "C97") (pin "2") (pinfunction "2_2") (pintype "passive"))
      (node (ref "C98") (pin "2") (pinfunction "2_2") (pintype "passive"))
      (node (ref "C99") (pin "2") (pinfunction "2_2") (pintype "passive"))
      (node (ref "D2") (pin "2") (pinfunction "K_2") (pintype "passive"))
      (node (ref "H1") (pin "2") (pintype "passive"))
      (node (ref "HIP1") (pin "14") (pinfunction "ALS_14") (pintype "tri_state"))
      (node (ref "HIP1") (pin "17") (pinfunction "BLS_17") (pintype "tri_state"))
      (node (ref "HIP1") (pin "3") (pinfunction "DIS_3") (pintype "tri_state"))
      (node (ref "HIP1") (pin "4") (pinfunction "VSS_4") (pintype "tri_state"))
      (node (ref "HIP2") (pin "14") (pinfunction "ALS_14") (pintype "tri_state"))
      (node (ref "HIP2") (pin "17") (pinfunction "BLS_17") (pintype "tri_state"))
      (node (ref "HIP2") (pin "3") (pinfunction "DIS_3") (pintype "tri_state"))
      (node (ref "HIP2") (pin "4") (pinfunction "VSS_4") (pintype "tri_state"))
      (node (ref "HIP3") (pin "14") (pinfunction "ALS_14") (pintype "tri_state"))
      (node (ref "HIP3") (pin "17") (pinfunction "BLS_17") (pintype "tri_state"))
      (node (ref "HIP3") (pin "3") (pinfunction "DIS_3") (pintype "tri_state"))
      (node (ref "HIP3") (pin "4") (pinfunction "VSS_4") (pintype "tri_state"))
      (node (ref "HIP4") (pin "14") (pinfunction "ALS_14") (pintype "tri_state"))
      (node (ref "HIP4") (pin "17") (pinfunction "BLS_17") (pintype "tri_state"))
      (node (ref "HIP4") (pin "3") (pinfunction "DIS_3") (pintype "tri_state"))
      (node (ref "HIP4") (pin "4") (pinfunction "VSS_4") (pintype "tri_state"))
      (node (ref "L5") (pin "1") (pinfunction "1_1") (pintype "passive"))
      (node (ref "LED1") (pin "2") (pinfunction "K_2") (pintype "passive"))
      (node (ref "LED2") (pin "2") (pinfunction "K_2") (pintype "passive"))
      (node (ref "Q11") (pin "3") (pinfunction "S_3") (pintype "input"))
      (node (ref "Q12") (pin "3") (pinfunction "S_3") (pintype "input"))
      (node (ref "Q15") (pin "3") (pinfunction "S_3") (pintype "input"))
      (node (ref "Q16") (pin "3") (pinfunction "S_3") (pintype "input"))
      (node (ref "Q3") (pin "3") (pinfunction "S_3") (pintype "input"))
      (node (ref "Q4") (pin "3") (pinfunction "S_3") (pintype "input"))
      (node (ref "Q7") (pin "3") (pinfunction "S_3") (pintype "input"))
      (node (ref "Q8") (pin "3") (pinfunction "S_3") (pintype "input"))
      (node (ref "R10") (pin "2") (pinfunction "2_2") (pintype "passive"))
      (node (ref "R13") (pin "2") (pinfunction "2_2") (pintype "passive"))
      (node (ref "R26") (pin "1") (pinfunction "1_1") (pintype "passive"))
      (node (ref "R27") (pin "1") (pinfunction "1_1") (pintype "passive"))
      (node (ref "R28") (pin "2") (pinfunction "2_2") (pintype "passive"))
      (node (ref "R29") (pin "2") (pinfunction "2_2") (pintype "passive"))
      (node (ref "R30") (pin "2") (pinfunction "2_2") (pintype "passive"))
      (node (ref "R33") (pin "2") (pinfunction "2_2") (pintype "passive"))
      (node (ref "R42") (pin "1") (pinfunction "1_1") (pintype "passive"))
      (node (ref "R43") (pin "1") (pinfunction "1_1") (pintype "passive"))
      (node (ref "R44") (pin "2") (pinfunction "2_2") (pintype "passive"))
      (node (ref "R45") (pin "2") (pinfunction "2_2") (pintype "passive"))
      (node (ref "R46") (pin "2") (pinfunction "2_2") (pintype "passive"))
      (node (ref "R49") (pin "2") (pinfunction "2_2") (pintype "passive"))
      (node (ref "R58") (pin "1") (pinfunction "1_1") (pintype "passive"))
      (node (ref "R59") (pin "1") (pinfunction "1_1") (pintype "passive"))
      (node (ref "R6") (pin "1") (pinfunction "1_1") (pintype "passive"))
      (node (ref "R60") (pin "2") (pinfunction "2_2") (pintype "passive"))
      (node (ref "R61") (pin "2") (pinfunction "2_2") (pintype "passive"))
      (node (ref "R62") (pin "2") (pinfunction "2_2") (pintype "passive"))
      (node (ref "R65") (pin "2") (pinfunction "2_2") (pintype "passive"))
      (node (ref "R7") (pin "1") (pinfunction "1_1") (pintype "passive"))
      (node (ref "R8") (pin "2") (pinfunction "2_2") (pintype "passive"))
      (node (ref "R9") (pin "2") (pinfunction "2_2") (pintype "passive"))
      (node (ref "U1") (pin "5") (pinfunction "GND_5") (pintype "passive"))
      (node (ref "U2") (pin "5") (pinfunction "GND_5") (pintype "passive"))
      (node (ref "U3") (pin "5") (pinfunction "GND_5") (pintype "passive"))
      (node (ref "U4") (pin "5") (pinfunction "GND_5") (pintype "passive"))
      (node (ref "U5") (pin "5") (pinfunction "GND_5") (pintype "passive"))
      (node (ref "U6") (pin "5") (pinfunction "GND_5") (pintype "passive"))
      (node (ref "U7") (pin "5") (pinfunction "GND_5") (pintype "passive"))
      (node (ref "U8") (pin "5") (pinfunction "GND_5") (pintype "passive"))
    )
    (net (code "45") (name "IC12V") (class "Default")
      (node (ref "1") (pin "1") (pinfunction "IN_1") (pintype "passive"))
      (node (ref "C1") (pin "2") (pinfunction "2_2") (pintype "passive"))
      (node (ref "C2") (pin "2") (pinfunction "2_2") (pintype "passive"))
      (node (ref "C3") (pin "2") (pinfunction "2_2") (pintype "passive"))
      (node (ref "C31") (pin "2") (pinfunction "2_2") (pintype "passive"))
      (node (ref "C32") (pin "2") (pinfunction "2_2") (pintype "passive"))
      (node (ref "C33") (pin "2") (pinfunction "2_2") (pintype "passive"))
      (node (ref "FU2") (pin "2") (pinfunction "2_2") (pintype "passive"))
      (node (ref "L11") (pin "2") (pinfunction "2_2") (pintype "passive"))
    )
    (net (code "46") (name "MCU") (class "Default")
      (node (ref "C24") (pin "1") (pinfunction "1_1") (pintype "passive"))
      (node (ref "C25") (pin "1") (pinfunction "1_1") (pintype "passive"))
      (node (ref "C26") (pin "1") (pinfunction "1_1") (pintype "passive"))
      (node (ref "H2") (pin "2") (pintype "passive"))
      (node (ref "L8") (pin "2") (pinfunction "2_2") (pintype "passive"))
      (node (ref "LED3") (pin "2") (pinfunction "K_2") (pintype "passive"))
    )
    (net (code "47") (name "MCU12V") (class "Default")
      (node (ref "C24") (pin "2") (pinfunction "2_2") (pintype "passive"))
      (node (ref "C25") (pin "2") (pinfunction "2_2") (pintype "passive"))
      (node (ref "C26") (pin "2") (pinfunction "2_2") (pintype "passive"))
      (node (ref "H2") (pin "1") (pintype "passive"))
      (node (ref "L4") (pin "2") (pinfunction "2_2") (pintype "passive"))
      (node (ref "R16") (pin "2") (pinfunction "2_2") (pintype "passive"))
    )
    (net (code "48") (name "Net-(1-OUT)") (class "Default")
      (node (ref "1") (pin "3") (pinfunction "OUT_3") (pintype "passive"))
      (node (ref "C4") (pin "1") (pinfunction "1_1") (pintype "passive"))
      (node (ref "C5") (pin "2") (pinfunction "2_2") (pintype "passive"))
      (node (ref "C6") (pin "2") (pinfunction "2_2") (pintype "passive"))
      (node (ref "FU1") (pin "1") (pinfunction "1_1") (pintype "passive"))
    )
    (net (code "49") (name "Net-(C18-Pad1)") (class "Default")
      (node (ref "C18") (pin "1") (pinfunction "1_1") (pintype "passive"))
      (node (ref "C19") (pin "1") (pinfunction "1_1") (pintype "passive"))
      (node (ref "L5") (pin "2") (pinfunction "2_2") (pintype "passive"))
      (node (ref "L6") (pin "1") (pinfunction "1_1") (pintype "passive"))
    )
    (net (code "50") (name "Net-(C18-Pad2)") (class "Default")
      (node (ref "C18") (pin "2") (pinfunction "2_2") (pintype "passive"))
      (node (ref "C19") (pin "2") (pinfunction "2_2") (pintype "passive"))
      (node (ref "L1") (pin "2") (pinfunction "2_2") (pintype "passive"))
      (node (ref "L2") (pin "1") (pinfunction "1_1") (pintype "passive"))
    )
    (net (code "51") (name "Net-(C20-Pad1)") (class "Default")
      (node (ref "C20") (pin "1") (pinfunction "1_1") (pintype "passive"))
      (node (ref "C21") (pin "1") (pinfunction "1_1") (pintype "passive"))
      (node (ref "L6") (pin "2") (pinfunction "2_2") (pintype "passive"))
      (node (ref "L7") (pin "1") (pinfunction "1_1") (pintype "passive"))
    )
    (net (code "52") (name "Net-(C20-Pad2)") (class "Default")
      (node (ref "C20") (pin "2") (pinfunction "2_2") (pintype "passive"))
      (node (ref "C21") (pin "2") (pinfunction "2_2") (pintype "passive"))
      (node (ref "L2") (pin "2") (pinfunction "2_2") (pintype "passive"))
      (node (ref "L3") (pin "1") (pinfunction "1_1") (pintype "passive"))
    )
    (net (code "53") (name "Net-(C22-Pad1)") (class "Default")
      (node (ref "C22") (pin "1") (pinfunction "1_1") (pintype "passive"))
      (node (ref "C23") (pin "1") (pinfunction "1_1") (pintype "passive"))
      (node (ref "L7") (pin "2") (pinfunction "2_2") (pintype "passive"))
      (node (ref "L8") (pin "1") (pinfunction "1_1") (pintype "passive"))
    )
    (net (code "54") (name "Net-(C22-Pad2)") (class "Default")
      (node (ref "C22") (pin "2") (pinfunction "2_2") (pintype "passive"))
      (node (ref "C23") (pin "2") (pinfunction "2_2") (pintype "passive"))
      (node (ref "L3") (pin "2") (pinfunction "2_2") (pintype "passive"))
      (node (ref "L4") (pin "1") (pinfunction "1_1") (pintype "passive"))
    )
    (net (code "55") (name "Net-(D1-K)") (class "Default")
      (node (ref "C7") (pin "1") (pinfunction "1_1") (pintype "passive"))
      (node (ref "D1") (pin "2") (pinfunction "K_2") (pintype "passive"))
      (node (ref "HIP1") (pin "1") (pinfunction "BHB_1") (pintype "tri_state"))
    )
    (net (code "56") (name "Net-(D2-A)") (class "Default")
      (node (ref "C4") (pin "2") (pinfunction "2_2") (pintype "passive"))
      (node (ref "C5") (pin "1") (pinfunction "1_1") (pintype "passive"))
      (node (ref "C6") (pin "1") (pinfunction "1_1") (pintype "passive"))
      (node (ref "D2") (pin "1") (pinfunction "A_1") (pintype "passive"))
    )
    (net (code "57") (name "Net-(D3-K)") (class "Default")
      (node (ref "C8") (pin "1") (pinfunction "1_1") (pintype "passive"))
      (node (ref "D3") (pin "2") (pinfunction "K_2") (pintype "passive"))
      (node (ref "HIP1") (pin "10") (pinfunction "AHB_10") (pintype "tri_state"))
    )
    (net (code "58") (name "Net-(D4-K)") (class "Default")
      (node (ref "C9") (pin "1") (pinfunction "1_1") (pintype "passive"))
      (node (ref "D4") (pin "2") (pinfunction "K_2") (pintype "passive"))
      (node (ref "HIP2") (pin "1") (pinfunction "BHB_1") (pintype "tri_state"))
    )
    (net (code "59") (name "Net-(D5-K)") (class "Default")
      (node (ref "C13") (pin "1") (pinfunction "1_1") (pintype "passive"))
      (node (ref "D5") (pin "2") (pinfunction "K_2") (pintype "passive"))
      (node (ref "HIP2") (pin "10") (pinfunction "AHB_10") (pintype "tri_state"))
    )
    (net (code "60") (name "Net-(D6-K)") (class "Default")
      (node (ref "C14") (pin "1") (pinfunction "1_1") (pintype "passive"))
      (node (ref "D6") (pin "2") (pinfunction "K_2") (pintype "passive"))
      (node (ref "HIP3") (pin "1") (pinfunction "BHB_1") (pintype "tri_state"))
    )
    (net (code "61") (name "Net-(D7-K)") (class "Default")
      (node (ref "C27") (pin "1") (pinfunction "1_1") (pintype "passive"))
      (node (ref "D7") (pin "2") (pinfunction "K_2") (pintype "passive"))
      (node (ref "HIP3") (pin "10") (pinfunction "AHB_10") (pintype "tri_state"))
    )
    (net (code "62") (name "Net-(D8-K)") (class "Default")
      (node (ref "C34") (pin "1") (pinfunction "1_1") (pintype "passive"))
      (node (ref "D8") (pin "2") (pinfunction "K_2") (pintype "passive"))
      (node (ref "HIP4") (pin "1") (pinfunction "BHB_1") (pintype "tri_state"))
    )
    (net (code "63") (name "Net-(D9-K)") (class "Default")
      (node (ref "C35") (pin "1") (pinfunction "1_1") (pintype "passive"))
      (node (ref "D9") (pin "2") (pinfunction "K_2") (pintype "passive"))
      (node (ref "HIP4") (pin "10") (pinfunction "AHB_10") (pintype "tri_state"))
    )
    (net (code "64") (name "Net-(DF1-B)") (class "Default")
      (node (ref "DF1") (pin "2") (pinfunction "B_2") (pintype "passive"))
      (node (ref "Q1") (pin "2") (pinfunction "D_2") (pintype "input"))
      (node (ref "Q2") (pin "2") (pinfunction "D_2") (pintype "input"))
    )
    (net (code "65") (name "Net-(DF2-B)") (class "Default")
      (node (ref "DF2") (pin "2") (pinfunction "B_2") (pintype "passive"))
      (node (ref "Q5") (pin "2") (pinfunction "D_2") (pintype "input"))
      (node (ref "Q6") (pin "2") (pinfunction "D_2") (pintype "input"))
    )
    (net (code "66") (name "Net-(DF3-B)") (class "Default")
      (node (ref "DF3") (pin "2") (pinfunction "B_2") (pintype "passive"))
      (node (ref "Q10") (pin "2") (pinfunction "D_2") (pintype "input"))
      (node (ref "Q9") (pin "2") (pinfunction "D_2") (pintype "input"))
    )
    (net (code "67") (name "Net-(DF4-B)") (class "Default")
      (node (ref "DF4") (pin "2") (pinfunction "B_2") (pintype "passive"))
      (node (ref "Q13") (pin "2") (pinfunction "D_2") (pintype "input"))
      (node (ref "Q14") (pin "2") (pinfunction "D_2") (pintype "input"))
    )
    (net (code "68") (name "Net-(HIP1-HDEL)") (class "Default")
      (node (ref "HIP1") (pin "8") (pinfunction "HDEL_8") (pintype "tri_state"))
      (node (ref "R8") (pin "1") (pinfunction "1_1") (pintype "passive"))
    )
    (net (code "69") (name "Net-(HIP1-LDEL)") (class "Default")
      (node (ref "HIP1") (pin "9") (pinfunction "LDEL_9") (pintype "tri_state"))
      (node (ref "R13") (pin "1") (pinfunction "1_1") (pintype "passive"))
    )
    (net (code "70") (name "Net-(HIP2-HDEL)") (class "Default")
      (node (ref "HIP2") (pin "8") (pinfunction "HDEL_8") (pintype "tri_state"))
      (node (ref "R28") (pin "1") (pinfunction "1_1") (pintype "passive"))
    )
    (net (code "71") (name "Net-(HIP2-LDEL)") (class "Default")
      (node (ref "HIP2") (pin "9") (pinfunction "LDEL_9") (pintype "tri_state"))
      (node (ref "R33") (pin "1") (pinfunction "1_1") (pintype "passive"))
    )
    (net (code "72") (name "Net-(HIP3-HDEL)") (class "Default")
      (node (ref "HIP3") (pin "8") (pinfunction "HDEL_8") (pintype "tri_state"))
      (node (ref "R44") (pin "1") (pinfunction "1_1") (pintype "passive"))
    )
    (net (code "73") (name "Net-(HIP3-LDEL)") (class "Default")
      (node (ref "HIP3") (pin "9") (pinfunction "LDEL_9") (pintype "tri_state"))
      (node (ref "R49") (pin "1") (pinfunction "1_1") (pintype "passive"))
    )
    (net (code "74") (name "Net-(HIP4-HDEL)") (class "Default")
      (node (ref "HIP4") (pin "8") (pinfunction "HDEL_8") (pintype "tri_state"))
      (node (ref "R60") (pin "1") (pinfunction "1_1") (pintype "passive"))
    )
    (net (code "75") (name "Net-(HIP4-LDEL)") (class "Default")
      (node (ref "HIP4") (pin "9") (pinfunction "LDEL_9") (pintype "tri_state"))
      (node (ref "R65") (pin "1") (pinfunction "1_1") (pintype "passive"))
    )
    (net (code "76") (name "Net-(L10-Pad1)") (class "Default")
      (node (ref "L10") (pin "1") (pinfunction "1_1") (pintype "passive"))
      (node (ref "L9") (pin "2") (pinfunction "2_2") (pintype "passive"))
    )
    (net (code "77") (name "Net-(L10-Pad2)") (class "Default")
      (node (ref "L10") (pin "2") (pinfunction "2_2") (pintype "passive"))
      (node (ref "L12") (pin "1") (pinfunction "1_1") (pintype "passive"))
    )
    (net (code "78") (name "Net-(L11-Pad1)") (class "Default")
      (node (ref "L11") (pin "1") (pinfunction "1_1") (pintype "passive"))
      (node (ref "L12") (pin "2") (pinfunction "2_2") (pintype "passive"))
    )
    (net (code "79") (name "Net-(LED1-A)") (class "Default")
      (node (ref "LED1") (pin "1") (pinfunction "A_1") (pintype "passive"))
      (node (ref "R14") (pin "1") (pinfunction "1_1") (pintype "passive"))
    )
    (net (code "80") (name "Net-(LED2-A)") (class "Default")
      (node (ref "LED2") (pin "1") (pinfunction "A_1") (pintype "passive"))
      (node (ref "R15") (pin "1") (pinfunction "1_1") (pintype "passive"))
    )
    (net (code "81") (name "Net-(LED3-A)") (class "Default")
      (node (ref "LED3") (pin "1") (pinfunction "A_1") (pintype "passive"))
      (node (ref "R16") (pin "1") (pinfunction "1_1") (pintype "passive"))
    )
    (net (code "82") (name "Net-(Q1-G)") (class "Default")
      (node (ref "Q1") (pin "1") (pinfunction "G_1") (pintype "input"))
      (node (ref "R4") (pin "2") (pinfunction "2_2") (pintype "passive"))
      (node (ref "R6") (pin "2") (pinfunction "2_2") (pintype "passive"))
    )
    (net (code "83") (name "Net-(Q2-G)") (class "Default")
      (node (ref "Q2") (pin "1") (pinfunction "G_1") (pintype "input"))
      (node (ref "R5") (pin "1") (pinfunction "1_1") (pintype "passive"))
      (node (ref "R7") (pin "2") (pinfunction "2_2") (pintype "passive"))
    )
    (net (code "84") (name "Net-(Q3-G)") (class "Default")
      (node (ref "Q3") (pin "1") (pinfunction "G_1") (pintype "input"))
      (node (ref "R11") (pin "1") (pinfunction "1_1") (pintype "passive"))
      (node (ref "R9") (pin "1") (pinfunction "1_1") (pintype "passive"))
    )
    (net (code "85") (name "Net-(Q4-G)") (class "Default")
      (node (ref "Q4") (pin "1") (pinfunction "G_1") (pintype "input"))
      (node (ref "R10") (pin "1") (pinfunction "1_1") (pintype "passive"))
      (node (ref "R12") (pin "1") (pinfunction "1_1") (pintype "passive"))
    )
    (net (code "86") (name "Net-(Q5-G)") (class "Default")
      (node (ref "Q5") (pin "1") (pinfunction "G_1") (pintype "input"))
      (node (ref "R24") (pin "2") (pinfunction "2_2") (pintype "passive"))
      (node (ref "R26") (pin "2") (pinfunction "2_2") (pintype "passive"))
    )
    (net (code "87") (name "Net-(Q6-G)") (class "Default")
      (node (ref "Q6") (pin "1") (pinfunction "G_1") (pintype "input"))
      (node (ref "R25") (pin "1") (pinfunction "1_1") (pintype "passive"))
      (node (ref "R27") (pin "2") (pinfunction "2_2") (pintype "passive"))
    )
    (net (code "88") (name "Net-(Q7-G)") (class "Default")
      (node (ref "Q7") (pin "1") (pinfunction "G_1") (pintype "input"))
      (node (ref "R29") (pin "1") (pinfunction "1_1") (pintype "passive"))
      (node (ref "R31") (pin "1") (pinfunction "1_1") (pintype "passive"))
    )
    (net (code "89") (name "Net-(Q8-G)") (class "Default")
      (node (ref "Q8") (pin "1") (pinfunction "G_1") (pintype "input"))
      (node (ref "R30") (pin "1") (pinfunction "1_1") (pintype "passive"))
      (node (ref "R32") (pin "1") (pinfunction "1_1") (pintype "passive"))
    )
    (net (code "90") (name "Net-(Q9-G)") (class "Default")
      (node (ref "Q9") (pin "1") (pinfunction "G_1") (pintype "input"))
      (node (ref "R40") (pin "2") (pinfunction "2_2") (pintype "passive"))
      (node (ref "R42") (pin "2") (pinfunction "2_2") (pintype "passive"))
    )
    (net (code "91") (name "Net-(Q10-G)") (class "Default")
      (node (ref "Q10") (pin "1") (pinfunction "G_1") (pintype "input"))
      (node (ref "R41") (pin "1") (pinfunction "1_1") (pintype "passive"))
      (node (ref "R43") (pin "2") (pinfunction "2_2") (pintype "passive"))
    )
    (net (code "92") (name "Net-(Q11-G)") (class "Default")
      (node (ref "Q11") (pin "1") (pinfunction "G_1") (pintype "input"))
      (node (ref "R45") (pin "1") (pinfunction "1_1") (pintype "passive"))
      (node (ref "R47") (pin "1") (pinfunction "1_1") (pintype "passive"))
    )
    (net (code "93") (name "Net-(Q12-G)") (class "Default")
      (node (ref "Q12") (pin "1") (pinfunction "G_1") (pintype "input"))
      (node (ref "R46") (pin "1") (pinfunction "1_1") (pintype "passive"))
      (node (ref "R48") (pin "1") (pinfunction "1_1") (pintype "passive"))
    )
    (net (code "94") (name "Net-(Q13-G)") (class "Default")
      (node (ref "Q13") (pin "1") (pinfunction "G_1") (pintype "input"))
      (node (ref "R56") (pin "2") (pinfunction "2_2") (pintype "passive"))
      (node (ref "R58") (pin "2") (pinfunction "2_2") (pintype "passive"))
    )
    (net (code "95") (name "Net-(Q14-G)") (class "Default")
      (node (ref "Q14") (pin "1") (pinfunction "G_1") (pintype "input"))
      (node (ref "R57") (pin "1") (pinfunction "1_1") (pintype "passive"))
      (node (ref "R59") (pin "2") (pinfunction "2_2") (pintype "passive"))
    )
    (net (code "96") (name "Net-(Q15-G)") (class "Default")
      (node (ref "Q15") (pin "1") (pinfunction "G_1") (pintype "input"))
      (node (ref "R61") (pin "1") (pinfunction "1_1") (pintype "passive"))
      (node (ref "R63") (pin "1") (pinfunction "1_1") (pintype "passive"))
    )
    (net (code "97") (name "Net-(Q16-G)") (class "Default")
      (node (ref "Q16") (pin "1") (pinfunction "G_1") (pintype "input"))
      (node (ref "R62") (pin "1") (pinfunction "1_1") (pintype "passive"))
      (node (ref "R64") (pin "1") (pinfunction "1_1") (pintype "passive"))
    )
    (net (code "98") (name "Net-(U1-V+)") (class "Default")
      (node (ref "R1") (pin "2") (pinfunction "2_2") (pintype "passive"))
      (node (ref "U1") (pin "2") (pinfunction "V+_2") (pintype "passive"))
    )
    (net (code "99") (name "Net-(U1-VE)") (class "Default")
      (node (ref "R2") (pin "2") (pinfunction "2_2") (pintype "passive"))
      (node (ref "U1") (pin "7") (pinfunction "VE_7") (pintype "passive"))
    )
    (net (code "100") (name "Net-(U2-V+)") (class "Default")
      (node (ref "R18") (pin "2") (pinfunction "2_2") (pintype "passive"))
      (node (ref "U2") (pin "2") (pinfunction "V+_2") (pintype "passive"))
    )
    (net (code "101") (name "Net-(U2-VE)") (class "Default")
      (node (ref "R19") (pin "2") (pinfunction "2_2") (pintype "passive"))
      (node (ref "U2") (pin "7") (pinfunction "VE_7") (pintype "passive"))
    )
    (net (code "102") (name "Net-(U3-V+)") (class "Default")
      (node (ref "R21") (pin "2") (pinfunction "2_2") (pintype "passive"))
      (node (ref "U3") (pin "2") (pinfunction "V+_2") (pintype "passive"))
    )
    (net (code "103") (name "Net-(U3-VE)") (class "Default")
      (node (ref "R22") (pin "2") (pinfunction "2_2") (pintype "passive"))
      (node (ref "U3") (pin "7") (pinfunction "VE_7") (pintype "passive"))
    )
    (net (code "104") (name "Net-(U4-V+)") (class "Default")
      (node (ref "R34") (pin "2") (pinfunction "2_2") (pintype "passive"))
      (node (ref "U4") (pin "2") (pinfunction "V+_2") (pintype "passive"))
    )
    (net (code "105") (name "Net-(U4-VE)") (class "Default")
      (node (ref "R35") (pin "2") (pinfunction "2_2") (pintype "passive"))
      (node (ref "U4") (pin "7") (pinfunction "VE_7") (pintype "passive"))
    )
    (net (code "106") (name "Net-(U5-V+)") (class "Default")
      (node (ref "R37") (pin "2") (pinfunction "2_2") (pintype "passive"))
      (node (ref "U5") (pin "2") (pinfunction "V+_2") (pintype "passive"))
    )
    (net (code "107") (name "Net-(U5-VE)") (class "Default")
      (node (ref "R38") (pin "2") (pinfunction "2_2") (pintype "passive"))
      (node (ref "U5") (pin "7") (pinfunction "VE_7") (pintype "passive"))
    )
    (net (code "108") (name "Net-(U6-V+)") (class "Default")
      (node (ref "R50") (pin "2") (pinfunction "2_2") (pintype "passive"))
      (node (ref "U6") (pin "2") (pinfunction "V+_2") (pintype "passive"))
    )
    (net (code "109") (name "Net-(U6-VE)") (class "Default")
      (node (ref "R51") (pin "2") (pinfunction "2_2") (pintype "passive"))
      (node (ref "U6") (pin "7") (pinfunction "VE_7") (pintype "passive"))
    )
    (net (code "110") (name "Net-(U7-V+)") (class "Default")
      (node (ref "R53") (pin "2") (pinfunction "2_2") (pintype "passive"))
      (node (ref "U7") (pin "2") (pinfunction "V+_2") (pintype "passive"))
    )
    (net (code "111") (name "Net-(U7-VE)") (class "Default")
      (node (ref "R54") (pin "2") (pinfunction "2_2") (pintype "passive"))
      (node (ref "U7") (pin "7") (pinfunction "VE_7") (pintype "passive"))
    )
    (net (code "112") (name "Net-(U8-V+)") (class "Default")
      (node (ref "R66") (pin "2") (pinfunction "2_2") (pintype "passive"))
      (node (ref "U8") (pin "2") (pinfunction "V+_2") (pintype "passive"))
    )
    (net (code "113") (name "Net-(U8-VE)") (class "Default")
      (node (ref "R67") (pin "2") (pinfunction "2_2") (pintype "passive"))
      (node (ref "U8") (pin "7") (pinfunction "VE_7") (pintype "passive"))
    )
    (net (code "114") (name "unconnected-(U1-NC-Pad1)") (class "Default")
      (node (ref "U1") (pin "1") (pinfunction "NC_1") (pintype "passive"))
    )
    (net (code "115") (name "unconnected-(U1-NC-Pad4)") (class "Default")
      (node (ref "U1") (pin "4") (pinfunction "NC_4") (pintype "passive"))
    )
    (net (code "116") (name "unconnected-(U2-NC-Pad1)") (class "Default")
      (node (ref "U2") (pin "1") (pinfunction "NC_1") (pintype "passive"))
    )
    (net (code "117") (name "unconnected-(U2-NC-Pad4)") (class "Default")
      (node (ref "U2") (pin "4") (pinfunction "NC_4") (pintype "passive"))
    )
    (net (code "118") (name "unconnected-(U3-NC-Pad1)") (class "Default")
      (node (ref "U3") (pin "1") (pinfunction "NC_1") (pintype "passive"))
    )
    (net (code "119") (name "unconnected-(U3-NC-Pad4)") (class "Default")
      (node (ref "U3") (pin "4") (pinfunction "NC_4") (pintype "passive"))
    )
    (net (code "120") (name "unconnected-(U4-NC-Pad1)") (class "Default")
      (node (ref "U4") (pin "1") (pinfunction "NC_1") (pintype "passive"))
    )
    (net (code "121") (name "unconnected-(U4-NC-Pad4)") (class "Default")
      (node (ref "U4") (pin "4") (pinfunction "NC_4") (pintype "passive"))
    )
    (net (code "122") (name "unconnected-(U5-NC-Pad1)") (class "Default")
      (node (ref "U5") (pin "1") (pinfunction "NC_1") (pintype "passive"))
    )
    (net (code "123") (name "unconnected-(U5-NC-Pad4)") (class "Default")
      (node (ref "U5") (pin "4") (pinfunction "NC_4") (pintype "passive"))
    )
    (net (code "124") (name "unconnected-(U6-NC-Pad1)") (class "Default")
      (node (ref "U6") (pin "1") (pinfunction "NC_1") (pintype "passive"))
    )
    (net (code "125") (name "unconnected-(U6-NC-Pad4)") (class "Default")
      (node (ref "U6") (pin "4") (pinfunction "NC_4") (pintype "passive"))
    )
    (net (code "126") (name "unconnected-(U7-NC-Pad1)") (class "Default")
      (node (ref "U7") (pin "1") (pinfunction "NC_1") (pintype "passive"))
    )
    (net (code "127") (name "unconnected-(U7-NC-Pad4)") (class "Default")
      (node (ref "U7") (pin "4") (pinfunction "NC_4") (pintype "passive"))
    )
    (net (code "128") (name "unconnected-(U8-NC-Pad1)") (class "Default")
      (node (ref "U8") (pin "1") (pinfunction "NC_1") (pintype "passive"))
    )
    (net (code "129") (name "unconnected-(U8-NC-Pad4)") (class "Default")
      (node (ref "U8") (pin "4") (pinfunction "NC_4") (pintype "passive"))
    )
    (net (code "130") (name "控地") (class "Default")
      (node (ref "U1") (pin "3") (pinfunction "V-_3") (pintype "passive"))
      (node (ref "U2") (pin "3") (pinfunction "V-_3") (pintype "passive"))
      (node (ref "U3") (pin "3") (pinfunction "V-_3") (pintype "passive"))
      (node (ref "U4") (pin "3") (pinfunction "V-_3") (pintype "passive"))
      (node (ref "U5") (pin "3") (pinfunction "V-_3") (pintype "passive"))
      (node (ref "U6") (pin "3") (pinfunction "V-_3") (pintype "passive"))
      (node (ref "U7") (pin "3") (pinfunction "V-_3") (pintype "passive"))
      (node (ref "U8") (pin "3") (pinfunction "V-_3") (pintype "passive"))
    )
  )
)
